# Dionysus_Power_Dave_McCoy_s_conflicted_c.net
KiCad netlist of a schematic drawn in Altium Designer
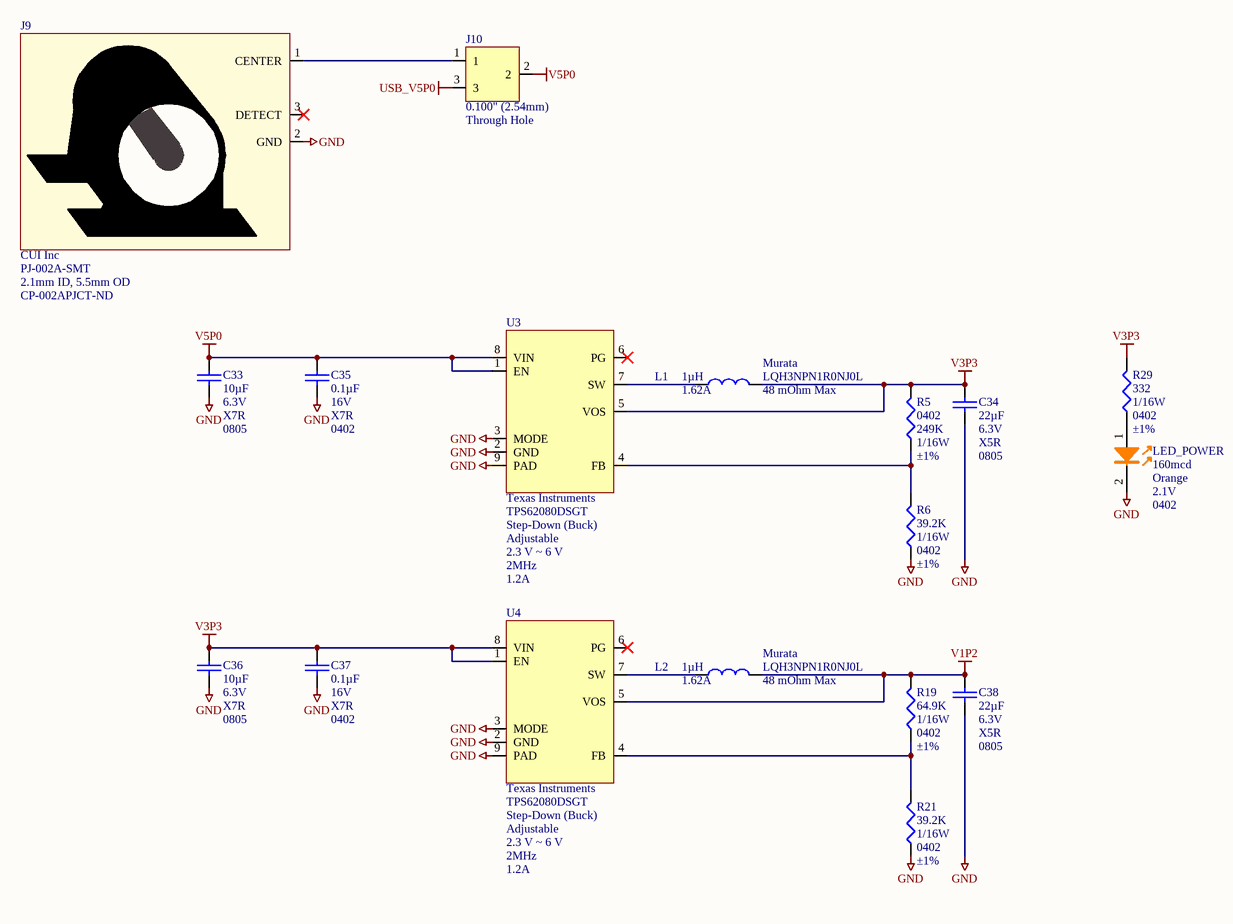
[diagram p0: Dionysus_Power (Dave McCoy's conflicted copy 2013-03-26).SchDoc]

(export (version "E")
  (design (tool "Eeschema 10.0.6"))
  (components
    (comp (ref "C33")
      (value "10uF")
      (footprint "C_ERA-0805")
      (description "CAP CER 10UF 6.3V X7R 10% 0805")
      (fields
        (field (name "MANUFACTURER") "Taiyo Yuden")
        (field (name "MANUFACTURER PART NUMBER") "JMK212BJ106KD-T")
        (field (name "CAPACITANCE") "10µF")
        (field (name "VOLTAGE - RATED") "6.3V")
        (field (name "TEMPERATURE COEFFICIENT") "X7R")
        (field (name "PACKAGE / CASE") "0805")
      )
      (libsource (lib "Main LibraryX") (part "C_0805_10UF_6.3V"))
    )
    (comp (ref "C34")
      (value "22uF")
      (footprint "C_ERA-0805")
      (description "CAP CER 22UF 6.3V X7R 10% 0805")
      (fields
        (field (name "MANUFACTURER") "AVX Corporation")
        (field (name "MANUFACTURER PART NUMBER") "08056D226MAT2A")
        (field (name "CAPACITANCE") "22µF")
        (field (name "VOLTAGE - RATED") "6.3V")
        (field (name "TEMPERATURE COEFFICIENT") "X5R")
        (field (name "PACKAGE / CASE") "0805")
      )
      (libsource (lib "Main LibraryX") (part "C_0805_22UF_6.3V"))
    )
    (comp (ref "C35")
      (value "0.1uF")
      (footprint "C_ERA-0402")
      (description "CAP CER .10UF 16V X7R 0402")
      (fields
        (field (name "MANUFACTURER") "TDK Corporation")
        (field (name "MANUFACTURER PART NUMBER") "C1005X7R1C104K")
        (field (name "CAPACITANCE") "0.1µF")
        (field (name "VOLTAGE - RATED") "16V")
        (field (name "TEMPERATURE COEFFICIENT") "X7R")
        (field (name "PACKAGE / CASE") "0402")
      )
      (libsource (lib "Main LibraryX") (part "C_0402_0.1UF_16V"))
    )
    (comp (ref "C36")
      (value "10uF")
      (footprint "C_ERA-0805")
      (description "CAP CER 10UF 6.3V X7R 10% 0805")
      (fields
        (field (name "MANUFACTURER") "Taiyo Yuden")
        (field (name "MANUFACTURER PART NUMBER") "JMK212BJ106KD-T")
        (field (name "CAPACITANCE") "10µF")
        (field (name "VOLTAGE - RATED") "6.3V")
        (field (name "TEMPERATURE COEFFICIENT") "X7R")
        (field (name "PACKAGE / CASE") "0805")
      )
      (libsource (lib "Main LibraryX") (part "C_0805_10UF_6.3V"))
    )
    (comp (ref "C37")
      (value "0.1uF")
      (footprint "C_ERA-0402")
      (description "CAP CER .10UF 16V X7R 0402")
      (fields
        (field (name "MANUFACTURER") "TDK Corporation")
        (field (name "MANUFACTURER PART NUMBER") "C1005X7R1C104K")
        (field (name "CAPACITANCE") "0.1µF")
        (field (name "VOLTAGE - RATED") "16V")
        (field (name "TEMPERATURE COEFFICIENT") "X7R")
        (field (name "PACKAGE / CASE") "0402")
      )
      (libsource (lib "Main LibraryX") (part "C_0402_0.1UF_16V"))
    )
    (comp (ref "C38")
      (value "22uF")
      (footprint "C_ERA-0805")
      (description "CAP CER 22UF 6.3V X7R 10% 0805")
      (fields
        (field (name "MANUFACTURER") "AVX Corporation")
        (field (name "MANUFACTURER PART NUMBER") "08056D226MAT2A")
        (field (name "CAPACITANCE") "22µF")
        (field (name "VOLTAGE - RATED") "6.3V")
        (field (name "TEMPERATURE COEFFICIENT") "X5R")
        (field (name "PACKAGE / CASE") "0805")
      )
      (libsource (lib "Main LibraryX") (part "C_0805_22UF_6.3V"))
    )
    (comp (ref "J9")
      (value "Barrel Jack")
      (footprint "PJ-002BH-SMT")
      (description "CONN POWER JACK 2.1X5.5MM SMD")
      (fields
        (field (name "MANUFACTURER") "CUI Inc")
        (field (name "MANUFACTURER PART NUMBER") "PJ-002A-SMT")
        (field (name "PLUG/MATING PLUG DIAMETER") "2.1mm ID, 5.5mm OD")
        (field (name "SUPPLIER PART NUMBER 1") "CP-002APJCT-ND")
      )
      (libsource (lib "Main LibraryX") (part "J_BARREL_JACK_2.1"))
    )
    (comp (ref "J10")
      (value "J_HDR1X3_JUMPER_SELECT")
      (footprint "HDR_1X3")
      (description "CONN HEADER .100\" 3POS TIN PCB")
      (fields
        (field (name "MANUFACTURER") "Samtec")
        (field (name "MANUFACTURER PART NUMBER") "TSW-103-07-T-S")
        (field (name "PITCH") "0.100\" (2.54mm)")
        (field (name "MOUNTING TYPE") "Through Hole")
      )
      (libsource (lib "Main LibraryX") (part "J_HDR1X3_JUMPER_SELECT"))
    )
    (comp (ref "L1")
      (value "1.0uH")
      (footprint "INDNRH1212")
      (description "INDUCTOR POWER 1.0UH 1620MA 1212")
      (fields
        (field (name "TOLERANCE") "±30%")
        (field (name "MANUFACTURER PART NUMBER") "LQH3NPN1R0NJ0L")
        (field (name "INDUCTANCE") "1µH")
        (field (name "CURRENT") "1.62A")
        (field (name "DC RESISTANCE (DCR)") "48 mOhm Max")
        (field (name "MANUFACTURER") "Murata")
      )
      (libsource (lib "Main Library") (part "L_1.0UH_1.62A"))
    )
    (comp (ref "L2")
      (value "1.0uH")
      (footprint "INDNRH1212")
      (description "INDUCTOR POWER 1.0UH 1620MA 1212")
      (fields
        (field (name "TOLERANCE") "±30%")
        (field (name "MANUFACTURER PART NUMBER") "LQH3NPN1R0NJ0L")
        (field (name "INDUCTANCE") "1µH")
        (field (name "CURRENT") "1.62A")
        (field (name "DC RESISTANCE (DCR)") "48 mOhm Max")
        (field (name "MANUFACTURER") "Murata")
      )
      (libsource (lib "Main Library") (part "L_1.0UH_1.62A"))
    )
    (comp (ref "LED_POWER")
      (value "LED_ORN_0402")
      (footprint "DIOM1005X07L_ORANGE")
      (description "LED 1X0.5MM 601NM ORN WTRCLR SMD")
      (fields
        (field (name "MANUFACTURER") "Kingbright Corp")
        (field (name "MANUFACTURER PART NUMBER") "APHHS1005SECK")
        (field (name "MILLICANDELA RATING") "160mcd")
        (field (name "COLOR") "Orange")
        (field (name "VOLTAGE - FORWARD (VF) TYP") "2.1V")
        (field (name "PACKAGE / CASE") "0402")
      )
      (libsource (lib "Main Library") (part "LED_ORN_0402"))
    )
    (comp (ref "R5")
      (value "R_0402_249K")
      (footprint "ERA-0402")
      (description "RES 249K OHM 1/16W 1% 0402 SMD")
      (fields
        (field (name "MANUFACTURER") "Yageo")
        (field (name "MANUFACTURER PART NUMBER") "RC0402FR-07249KL")
        (field (name "PACKAGE / CASE") "0402")
        (field (name "RESISTANCE (OHMS)") "249K")
        (field (name "POWER (WATTS)") "1/16W")
        (field (name "TOLERANCE") "±1%")
      )
      (libsource (lib "Main LibraryX") (part "R_0402_249K"))
    )
    (comp (ref "R6")
      (value "R_0402_39.2K")
      (footprint "ERA-0402")
      (description "RES 39.2K OHM 1/16W 1% 0402 SMD")
      (fields
        (field (name "RESISTANCE IN OHMS") "39.2K")
        (field (name "POWER (WATTS)") "1/16W")
        (field (name "CASE") "0402")
        (field (name "TOLERANCE") "±1%")
        (field (name "MANUFACTURER") "Yageo")
        (field (name "MANUFACTURER PART NUMBER") "RC0402FR-0739K2L")
      )
      (libsource (lib "Main LibraryX") (part "R_0402_39.2K"))
    )
    (comp (ref "R19")
      (value "R_0402_64.9K")
      (footprint "ERA-0402")
      (description "RES 64.9K OHM 1/16W 1% 0402 SMD")
      (fields
        (field (name "MANUFACTURER") "Yageo")
        (field (name "MANUFACTURER PART NUMBER") "RC0402FR-0764K9L")
        (field (name "RESISTANCE IN OHMS") "64.9K")
        (field (name "POWER (WATTS)") "1/16W")
        (field (name "CASE") "0402")
        (field (name "TOLERANCE") "±1%")
      )
      (libsource (lib "Main Library") (part "R_0402_64.9K"))
    )
    (comp (ref "R21")
      (value "R_0402_39.2K")
      (footprint "ERA-0402")
      (description "RES 39.2K OHM 1/16W 1% 0402 SMD")
      (fields
        (field (name "RESISTANCE IN OHMS") "39.2K")
        (field (name "POWER (WATTS)") "1/16W")
        (field (name "CASE") "0402")
        (field (name "TOLERANCE") "±1%")
        (field (name "MANUFACTURER") "Yageo")
        (field (name "MANUFACTURER PART NUMBER") "RC0402FR-0739K2L")
      )
      (libsource (lib "Main LibraryX") (part "R_0402_39.2K"))
    )
    (comp (ref "R29")
      (value "R_0402_332.0")
      (footprint "ERA-0402")
      (description "RES 332 OHM 1/16W 1% 0402 SMD")
      (fields
        (field (name "MANUFACTURER") "Vishay/Dale")
        (field (name "MANUFACTURER PART NUMBER") "CRCW0402332RFKED")
        (field (name "RESISTANCE IN OHMS") "332")
        (field (name "POWER (WATTS)") "1/16W")
        (field (name "CASE") "0402")
        (field (name "TOLERANCE") "±1%")
      )
      (libsource (lib "Main LibraryX") (part "R_0402_332.0"))
    )
    (comp (ref "U3")
      (value "TPS62080")
      (footprint "QFN50P200X200X80-8L")
      (description "IC BUCK SYNC ADJ 1.2A 8WSON")
      (fields
        (field (name "MANUFACTURER") "Texas Instruments")
        (field (name "MANUFACTURER PART NUMBER") "TPS62080DSGT")
        (field (name "TYPE") "Step-Down (Buck)")
        (field (name "OUTPUT TYPE") "Adjustable")
        (field (name "VOLTAGE - INPUT") "2.3 V ~ 6 V")
        (field (name "FREQUENCY - SWITCHING") "2MHz")
        (field (name "CURRENT - OUTPUT") "1.2A")
      )
      (libsource (lib "Main Library") (part "U_TPS62080"))
    )
    (comp (ref "U4")
      (value "TPS62080")
      (footprint "QFN50P200X200X80-8L")
      (description "IC BUCK SYNC ADJ 1.2A 8WSON")
      (fields
        (field (name "MANUFACTURER") "Texas Instruments")
        (field (name "MANUFACTURER PART NUMBER") "TPS62080DSGT")
        (field (name "TYPE") "Step-Down (Buck)")
        (field (name "OUTPUT TYPE") "Adjustable")
        (field (name "VOLTAGE - INPUT") "2.3 V ~ 6 V")
        (field (name "FREQUENCY - SWITCHING") "2MHz")
        (field (name "CURRENT - OUTPUT") "1.2A")
      )
      (libsource (lib "Main Library") (part "U_TPS62080"))
    )
  )
  (nets
    (net (code "1") (name "GND") (class "Default")
      (node (ref "C33") (pin "1") (pinfunction "1_1") (pintype "passive"))
      (node (ref "C34") (pin "1") (pinfunction "1_1") (pintype "passive"))
      (node (ref "C35") (pin "1") (pinfunction "1_1") (pintype "passive"))
      (node (ref "C36") (pin "1") (pinfunction "1_1") (pintype "passive"))
      (node (ref "C37") (pin "1") (pinfunction "1_1") (pintype "passive"))
      (node (ref "C38") (pin "1") (pinfunction "1_1") (pintype "passive"))
      (node (ref "J9") (pin "2") (pinfunction "GND_2") (pintype "passive"))
      (node (ref "LED_POWER") (pin "2") (pinfunction "2_2") (pintype "passive"))
      (node (ref "R21") (pin "2") (pinfunction "2_2") (pintype "passive"))
      (node (ref "R6") (pin "2") (pinfunction "2_2") (pintype "passive"))
      (node (ref "U3") (pin "2") (pinfunction "GND_2") (pintype "passive"))
      (node (ref "U3") (pin "3") (pinfunction "MODE_3") (pintype "passive"))
      (node (ref "U3") (pin "9") (pinfunction "PAD_9") (pintype "passive"))
      (node (ref "U4") (pin "2") (pinfunction "GND_2") (pintype "passive"))
      (node (ref "U4") (pin "3") (pinfunction "MODE_3") (pintype "passive"))
      (node (ref "U4") (pin "9") (pinfunction "PAD_9") (pintype "passive"))
    )
    (net (code "2") (name "Net-(J9-CENTER)") (class "Default")
      (node (ref "J10") (pin "1") (pinfunction "1_1") (pintype "passive"))
      (node (ref "J9") (pin "1") (pinfunction "CENTER_1") (pintype "passive"))
    )
    (net (code "3") (name "Net-(LED_POWER-Pad1)") (class "Default")
      (node (ref "LED_POWER") (pin "1") (pinfunction "1_1") (pintype "passive"))
      (node (ref "R29") (pin "2") (pinfunction "2_2") (pintype "passive"))
    )
    (net (code "4") (name "Net-(U3-FB)") (class "Default")
      (node (ref "R5") (pin "2") (pinfunction "2_2") (pintype "passive"))
      (node (ref "R6") (pin "1") (pinfunction "1_1") (pintype "passive"))
      (node (ref "U3") (pin "4") (pinfunction "FB_4") (pintype "passive"))
    )
    (net (code "5") (name "Net-(U3-SW)") (class "Default")
      (node (ref "L1") (pin "1") (pintype "passive"))
      (node (ref "U3") (pin "7") (pinfunction "SW_7") (pintype "passive"))
    )
    (net (code "6") (name "Net-(U4-FB)") (class "Default")
      (node (ref "R19") (pin "2") (pinfunction "2_2") (pintype "passive"))
      (node (ref "R21") (pin "1") (pinfunction "1_1") (pintype "passive"))
      (node (ref "U4") (pin "4") (pinfunction "FB_4") (pintype "passive"))
    )
    (net (code "7") (name "Net-(U4-SW)") (class "Default")
      (node (ref "L2") (pin "1") (pintype "passive"))
      (node (ref "U4") (pin "7") (pinfunction "SW_7") (pintype "passive"))
    )
    (net (code "8") (name "USB_V5P0") (class "Default")
      (node (ref "J10") (pin "3") (pinfunction "3_3") (pintype "passive"))
    )
    (net (code "9") (name "V1P2") (class "Default")
      (node (ref "C38") (pin "2") (pinfunction "2_2") (pintype "passive"))
      (node (ref "L2") (pin "2") (pintype "passive"))
      (node (ref "R19") (pin "1") (pinfunction "1_1") (pintype "passive"))
      (node (ref "U4") (pin "5") (pinfunction "VOS_5") (pintype "passive"))
    )
    (net (code "10") (name "V3P3") (class "Default")
      (node (ref "C34") (pin "2") (pinfunction "2_2") (pintype "passive"))
      (node (ref "C36") (pin "2") (pinfunction "2_2") (pintype "passive"))
      (node (ref "C37") (pin "2") (pinfunction "2_2") (pintype "passive"))
      (node (ref "L1") (pin "2") (pintype "passive"))
      (node (ref "R29") (pin "1") (pinfunction "1_1") (pintype "passive"))
      (node (ref "R5") (pin "1") (pinfunction "1_1") (pintype "passive"))
      (node (ref "U3") (pin "5") (pinfunction "VOS_5") (pintype "passive"))
      (node (ref "U4") (pin "1") (pinfunction "EN_1") (pintype "passive"))
      (node (ref "U4") (pin "8") (pinfunction "VIN_8") (pintype "passive"))
    )
    (net (code "11") (name "V5P0") (class "Default")
      (node (ref "C33") (pin "2") (pinfunction "2_2") (pintype "passive"))
      (node (ref "C35") (pin "2") (pinfunction "2_2") (pintype "passive"))
      (node (ref "J10") (pin "2") (pinfunction "2_2") (pintype "passive"))
      (node (ref "U3") (pin "1") (pinfunction "EN_1") (pintype "passive"))
      (node (ref "U3") (pin "8") (pinfunction "VIN_8") (pintype "passive"))
    )
    (net (code "12") (name "unconnected-(J9-DETECT-Pad3)") (class "Default")
      (node (ref "J9") (pin "3") (pinfunction "DETECT_3") (pintype "passive+no_connect"))
    )
    (net (code "13") (name "unconnected-(U3-PG-Pad6)") (class "Default")
      (node (ref "U3") (pin "6") (pinfunction "PG_6") (pintype "passive+no_connect"))
    )
    (net (code "14") (name "unconnected-(U4-PG-Pad6)") (class "Default")
      (node (ref "U4") (pin "6") (pinfunction "PG_6") (pintype "passive+no_connect"))
    )
  )
)
